# Voltage_Regulation_TI.net
KiCad netlist of a schematic drawn in Altium Designer
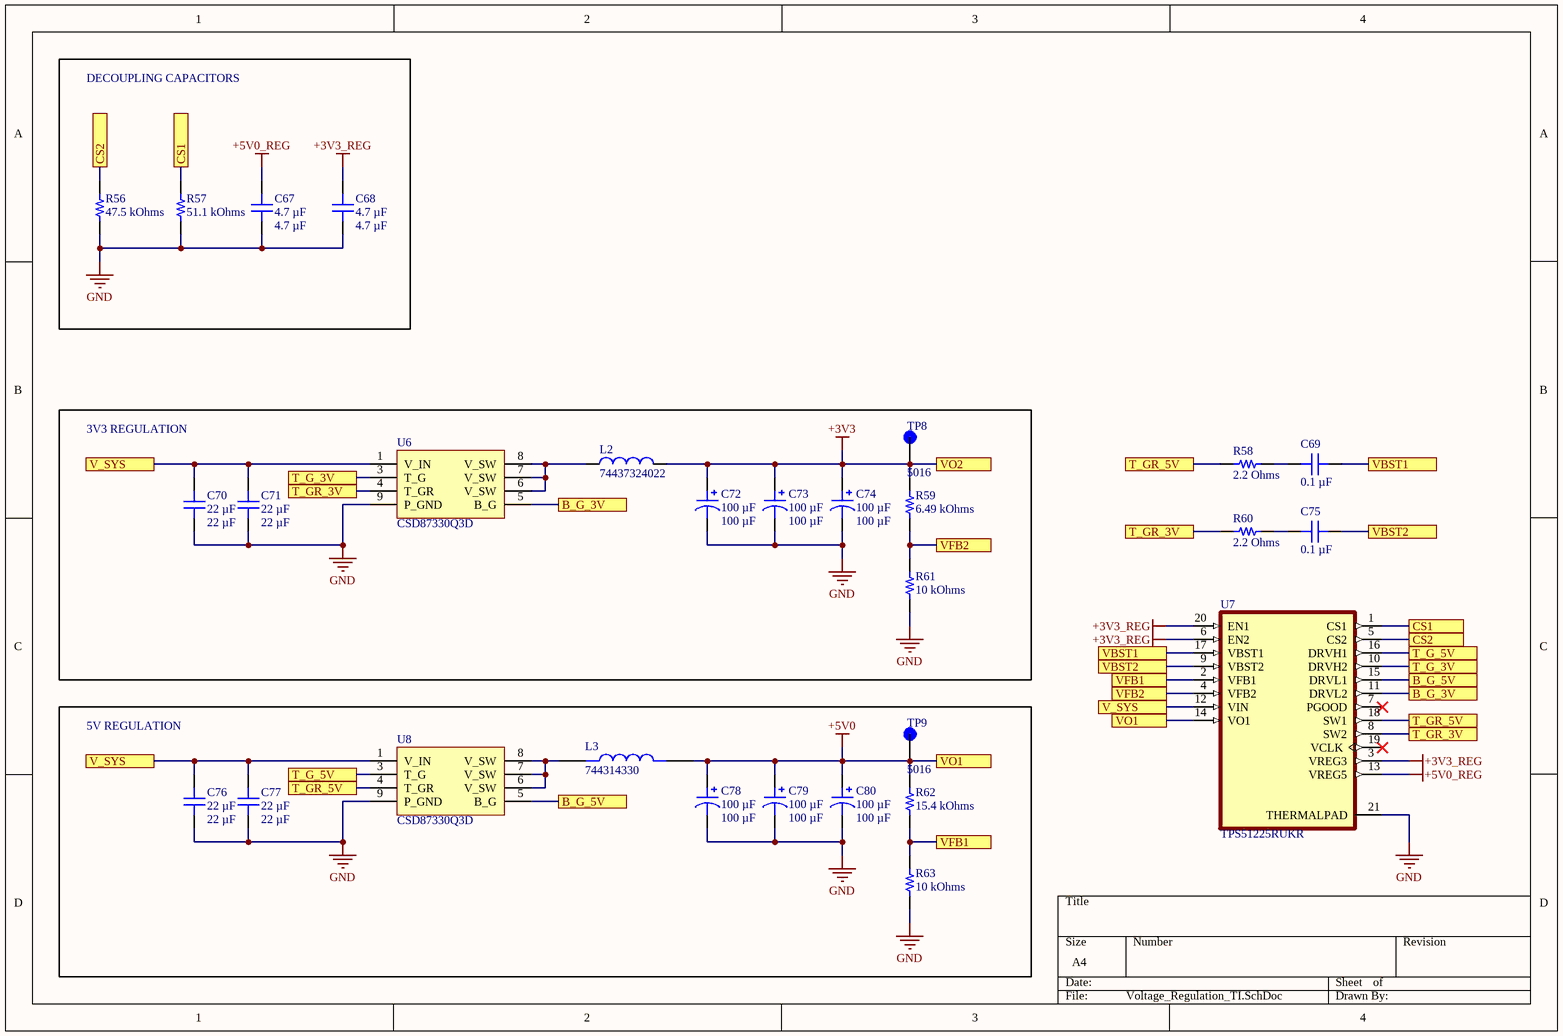
[diagram p0: Voltage_Regulation_TI.SchDoc]

(export (version "E")
  (design (tool "Eeschema 10.0.6"))
  (components
    (comp (ref "C67")
      (value "4.7 µF")
      (footprint "CAP 0402_1005")
      (description "CAP CER 4.7UF 16V X5R 0402")
      (fields
        (field (name "PART NUMBER") "CL05A475MO5NUNC")
        (field (name "ALTIUM_VALUE") "4.7 µF")
        (field (name "MANUFACTURER") "Samsung Electro-Mechanics")
      )
      (libsource (lib "Celestial Altium Library - altium_library") (part "Capacitor"))
    )
    (comp (ref "C68")
      (value "4.7 µF")
      (footprint "CAP 0402_1005")
      (description "CAP CER 4.7UF 16V X5R 0402")
      (fields
        (field (name "PART NUMBER") "CL05A475MO5NUNC")
        (field (name "ALTIUM_VALUE") "4.7 µF")
        (field (name "MANUFACTURER") "Samsung Electro-Mechanics")
      )
      (libsource (lib "Celestial Altium Library - altium_library") (part "Capacitor"))
    )
    (comp (ref "C69")
      (value "0.1 µF")
      (footprint "CAP 0402_1005")
      (description "CAP CER 0.1UF 6.3V X5R 0402")
      (fields (field (name "PART NUMBER") "885012105001") (field (name "MANUFACTURER") "Würth Elektronik"))
      (libsource (lib "Celestial Altium Library - altium_library") (part "Capacitor"))
    )
    (comp (ref "C70")
      (value "22 µF")
      (footprint "CAP 0805_2012")
      (description "CAP CER 22UF 35V X5R 0805")
      (fields
        (field (name "PART NUMBER") "C2012X5R1V226M125AC")
        (field (name "ALTIUM_VALUE") "22 µF")
        (field (name "MANUFACTURER") "TDK Corporation")
      )
      (libsource (lib "Celestial Altium Library - altium_library") (part "Capacitor"))
    )
    (comp (ref "C71")
      (value "22 µF")
      (footprint "CAP 0805_2012")
      (description "CAP CER 22UF 35V X5R 0805")
      (fields
        (field (name "PART NUMBER") "C2012X5R1V226M125AC")
        (field (name "ALTIUM_VALUE") "22 µF")
        (field (name "MANUFACTURER") "TDK Corporation")
      )
      (libsource (lib "Celestial Altium Library - altium_library") (part "Capacitor"))
    )
    (comp (ref "C72")
      (value "100 µF")
      (footprint "CAP POL 1411_3528")
      (description "CAP TANT 100UF 20% 10V 1411")
      (fields
        (field (name "PART NUMBER") "ATCC-211B-010-107M-T")
        (field (name "ALTIUM_VALUE") "100 µF")
        (field (name "MANUFACTURER") "Abracon LLC")
      )
      (libsource (lib "Celestial Altium Library - altium_library") (part "Polarised Capacitor"))
    )
    (comp (ref "C73")
      (value "100 µF")
      (footprint "CAP POL 1411_3528")
      (description "CAP TANT 100UF 20% 10V 1411")
      (fields
        (field (name "PART NUMBER") "ATCC-211B-010-107M-T")
        (field (name "ALTIUM_VALUE") "100 µF")
        (field (name "MANUFACTURER") "Abracon LLC")
      )
      (libsource (lib "Celestial Altium Library - altium_library") (part "Polarised Capacitor"))
    )
    (comp (ref "C74")
      (value "100 µF")
      (footprint "CAP POL 1411_3528")
      (description "CAP TANT 100UF 20% 10V 1411")
      (fields
        (field (name "PART NUMBER") "ATCC-211B-010-107M-T")
        (field (name "ALTIUM_VALUE") "100 µF")
        (field (name "MANUFACTURER") "Abracon LLC")
      )
      (libsource (lib "Celestial Altium Library - altium_library") (part "Polarised Capacitor"))
    )
    (comp (ref "C75")
      (value "0.1 µF")
      (footprint "CAP 0402_1005")
      (description "CAP CER 0.1UF 6.3V X5R 0402")
      (fields (field (name "PART NUMBER") "885012105001") (field (name "MANUFACTURER") "Würth Elektronik"))
      (libsource (lib "Celestial Altium Library - altium_library") (part "Capacitor"))
    )
    (comp (ref "C76")
      (value "22 µF")
      (footprint "CAP 0805_2012")
      (description "CAP CER 22UF 35V X5R 0805")
      (fields
        (field (name "PART NUMBER") "C2012X5R1V226M125AC")
        (field (name "ALTIUM_VALUE") "22 µF")
        (field (name "MANUFACTURER") "TDK Corporation")
      )
      (libsource (lib "Celestial Altium Library - altium_library") (part "Capacitor"))
    )
    (comp (ref "C77")
      (value "22 µF")
      (footprint "CAP 0805_2012")
      (description "CAP CER 22UF 35V X5R 0805")
      (fields
        (field (name "PART NUMBER") "C2012X5R1V226M125AC")
        (field (name "ALTIUM_VALUE") "22 µF")
        (field (name "MANUFACTURER") "TDK Corporation")
      )
      (libsource (lib "Celestial Altium Library - altium_library") (part "Capacitor"))
    )
    (comp (ref "C78")
      (value "100 µF")
      (footprint "CAP POL 1411_3528")
      (description "CAP TANT 100UF 20% 10V 1411")
      (fields
        (field (name "PART NUMBER") "ATCC-211B-010-107M-T")
        (field (name "ALTIUM_VALUE") "100 µF")
        (field (name "MANUFACTURER") "Abracon LLC")
      )
      (libsource (lib "Celestial Altium Library - altium_library") (part "Polarised Capacitor"))
    )
    (comp (ref "C79")
      (value "100 µF")
      (footprint "CAP POL 1411_3528")
      (description "CAP TANT 100UF 20% 10V 1411")
      (fields
        (field (name "PART NUMBER") "ATCC-211B-010-107M-T")
        (field (name "ALTIUM_VALUE") "100 µF")
        (field (name "MANUFACTURER") "Abracon LLC")
      )
      (libsource (lib "Celestial Altium Library - altium_library") (part "Polarised Capacitor"))
    )
    (comp (ref "C80")
      (value "100 µF")
      (footprint "CAP POL 1411_3528")
      (description "CAP TANT 100UF 20% 10V 1411")
      (fields
        (field (name "PART NUMBER") "ATCC-211B-010-107M-T")
        (field (name "ALTIUM_VALUE") "100 µF")
        (field (name "MANUFACTURER") "Abracon LLC")
      )
      (libsource (lib "Celestial Altium Library - altium_library") (part "Polarised Capacitor"))
    )
    (comp (ref "L2")
      (value "74437324022")
      (footprint "74437324022:IND_74437324022")
      (description "LHMI Inductor 4020 2.2uH 5.0A 27.0mOhm")
      (fields (field (name "MF") "{'manufacturer': u'~{W}xfcrth Elektronik'}"))
      (libsource (lib "*") (part "74437324022"))
    )
    (comp (ref "L3")
      (value "744314330")
      (footprint "744314330:IND_744314330")
      (description "Inductor SMD 7050 3.3µH 9 A Wuerth Elektronik WE-HCI 744314330 1 pc(s)")
      (fields (field (name "MF") "{'manufacturer': u'Wurth Electronics'}"))
      (libsource (lib "*") (part "744314330"))
    )
    (comp (ref "R56")
      (value "47.5 kOhms")
      (footprint "RES 0402_1005")
      (description "RES 47.5K OHM 1% 1/16W 0402")
      (fields (field (name "PART NUMBER") "RC0402FR-0747K5L") (field (name "MANUFACTURER") "Yageo"))
      (libsource (lib "Celestial Altium Library - altium_library") (part "Resistor"))
    )
    (comp (ref "R57")
      (value "51.1 kOhms")
      (footprint "RES 0402_1005")
      (description "RES SMD 51.1K OHM 1% 1/16W 0402")
      (fields (field (name "PART NUMBER") "CR0402-FX-5112GLF") (field (name "MANUFACTURER") "Bourns Inc."))
      (libsource (lib "Celestial Altium Library - altium_library") (part "Resistor"))
    )
    (comp (ref "R58")
      (value "2.2 Ohms")
      (footprint "RES 0402_1005")
      (description "RES 2.2 OHM 5% 1/16W 0402")
      (fields (field (name "PART NUMBER") "RC0402JR-072R2L") (field (name "MANUFACTURER") "Yageo"))
      (libsource (lib "Celestial Altium Library - altium_library") (part "Resistor"))
    )
    (comp (ref "R59")
      (value "6.49 kOhms")
      (footprint "RES 0402_1005")
      (description "RES 6.49K OHM 1% 1/16W 0402")
      (fields (field (name "PART NUMBER") "RC0402FR-076K49L") (field (name "MANUFACTURER") "Yageo"))
      (libsource (lib "Celestial Altium Library - altium_library") (part "Resistor"))
    )
    (comp (ref "R60")
      (value "2.2 Ohms")
      (footprint "RES 0402_1005")
      (description "RES 2.2 OHM 5% 1/16W 0402")
      (fields (field (name "PART NUMBER") "RC0402JR-072R2L") (field (name "MANUFACTURER") "Yageo"))
      (libsource (lib "Celestial Altium Library - altium_library") (part "Resistor"))
    )
    (comp (ref "R61")
      (value "10 kOhms")
      (footprint "RES 0402_1005")
      (description "RES 10K OHM 5% 1/16W 0402")
      (fields (field (name "PART NUMBER") "RC0402JR-1310KL") (field (name "MANUFACTURER") "Yageo"))
      (libsource (lib "Celestial Altium Library - altium_library") (part "Resistor"))
    )
    (comp (ref "R62")
      (value "15.4 kOhms")
      (footprint "RES 0402_1005")
      (description "RES 15.4K OHM 1% 1/16W 0402")
      (fields (field (name "PART NUMBER") "RC0402FR-0715K4L") (field (name "MANUFACTURER") "Yageo"))
      (libsource (lib "Celestial Altium Library - altium_library") (part "Resistor"))
    )
    (comp (ref "R63")
      (value "10 kOhms")
      (footprint "RES 0402_1005")
      (description "RES 10K OHM 5% 1/16W 0402")
      (fields (field (name "PART NUMBER") "RC0402JR-1310KL") (field (name "MANUFACTURER") "Yageo"))
      (libsource (lib "Celestial Altium Library - altium_library") (part "Resistor"))
    )
    (comp (ref "TP8")
      (value "5016")
      (footprint "5016:KEYSTONE_5016")
      (fields (field (name "MF") "{'manufacturer': u'Keystone Electronics'}"))
      (libsource (lib "*") (part "5016"))
    )
    (comp (ref "TP9")
      (value "5016")
      (footprint "5016:KEYSTONE_5016")
      (fields (field (name "MF") "{'manufacturer': u'Keystone Electronics'}"))
      (libsource (lib "*") (part "5016"))
    )
    (comp (ref "U6")
      (value "CSD87330Q3D")
      (footprint "Q3D")
      (description "Synchronous Buck NexFET™ Power Block")
      (libsource (lib "Schlib2") (part "CSD87330Q3D"))
    )
    (comp (ref "U7")
      (value "TPS51225RUKR")
      (footprint "TPS51225RUKR:QFN40P300X300X80-21N")
      (fields (field (name "MF") "{'manufacturer': u'Texas Instruments'}"))
      (libsource (lib "*") (part "TPS51225RUKR"))
    )
    (comp (ref "U8")
      (value "CSD87330Q3D")
      (footprint "Q3D")
      (description "Synchronous Buck NexFET™ Power Block")
      (libsource (lib "Schlib2") (part "CSD87330Q3D"))
    )
  )
  (nets
    (net (code "1") (name "+3V3") (class "Default")
      (node (ref "C72") (pin "1") (pinfunction "1_1") (pintype "passive"))
      (node (ref "C73") (pin "1") (pinfunction "1_1") (pintype "passive"))
      (node (ref "C74") (pin "1") (pinfunction "1_1") (pintype "passive"))
      (node (ref "L2") (pin "2") (pinfunction "2_2") (pintype "passive"))
      (node (ref "R59") (pin "2") (pinfunction "2_2") (pintype "passive"))
      (node (ref "TP8") (pin "TP") (pinfunction "TP_TP") (pintype "passive"))
    )
    (net (code "2") (name "+3V3_REG") (class "Default")
      (node (ref "C68") (pin "2") (pinfunction "2_2") (pintype "passive"))
      (node (ref "U7") (pin "20") (pinfunction "EN1_20") (pintype "input"))
      (node (ref "U7") (pin "3") (pinfunction "VREG3_3") (pintype "output"))
      (node (ref "U7") (pin "6") (pinfunction "EN2_6") (pintype "input"))
    )
    (net (code "3") (name "+5V0") (class "Default")
      (node (ref "C78") (pin "1") (pinfunction "1_1") (pintype "passive"))
      (node (ref "C79") (pin "1") (pinfunction "1_1") (pintype "passive"))
      (node (ref "C80") (pin "1") (pinfunction "1_1") (pintype "passive"))
      (node (ref "L3") (pin "2") (pinfunction "2_2") (pintype "passive"))
      (node (ref "R62") (pin "2") (pinfunction "2_2") (pintype "passive"))
      (node (ref "TP9") (pin "TP") (pinfunction "TP_TP") (pintype "passive"))
      (node (ref "U7") (pin "14") (pinfunction "VO1_14") (pintype "input"))
    )
    (net (code "4") (name "+5V0_REG") (class "Default")
      (node (ref "C67") (pin "2") (pinfunction "2_2") (pintype "passive"))
      (node (ref "U7") (pin "13") (pinfunction "VREG5_13") (pintype "output"))
    )
    (net (code "5") (name "/B_G_3V") (class "Default")
      (node (ref "U6") (pin "5") (pinfunction "B_G_5") (pintype "passive"))
      (node (ref "U7") (pin "11") (pinfunction "DRVL2_11") (pintype "output"))
    )
    (net (code "6") (name "/B_G_5V") (class "Default")
      (node (ref "U7") (pin "15") (pinfunction "DRVL1_15") (pintype "output"))
      (node (ref "U8") (pin "5") (pinfunction "B_G_5") (pintype "passive"))
    )
    (net (code "7") (name "/CS1") (class "Default")
      (node (ref "R57") (pin "2") (pinfunction "2_2") (pintype "passive"))
      (node (ref "U7") (pin "1") (pinfunction "CS1_1") (pintype "output"))
    )
    (net (code "8") (name "/CS2") (class "Default")
      (node (ref "R56") (pin "2") (pinfunction "2_2") (pintype "passive"))
      (node (ref "U7") (pin "5") (pinfunction "CS2_5") (pintype "output"))
    )
    (net (code "9") (name "/T_GR_3V") (class "Default")
      (node (ref "R60") (pin "1") (pinfunction "1_1") (pintype "passive"))
      (node (ref "U6") (pin "4") (pinfunction "T_GR_4") (pintype "passive"))
      (node (ref "U7") (pin "8") (pinfunction "SW2_8") (pintype "output"))
    )
    (net (code "10") (name "/T_GR_5V") (class "Default")
      (node (ref "R58") (pin "1") (pinfunction "1_1") (pintype "passive"))
      (node (ref "U7") (pin "18") (pinfunction "SW1_18") (pintype "output"))
      (node (ref "U8") (pin "4") (pinfunction "T_GR_4") (pintype "passive"))
    )
    (net (code "11") (name "/T_G_3V") (class "Default")
      (node (ref "U6") (pin "3") (pinfunction "T_G_3") (pintype "passive"))
      (node (ref "U7") (pin "10") (pinfunction "DRVH2_10") (pintype "output"))
    )
    (net (code "12") (name "/T_G_5V") (class "Default")
      (node (ref "U7") (pin "16") (pinfunction "DRVH1_16") (pintype "output"))
      (node (ref "U8") (pin "3") (pinfunction "T_G_3") (pintype "passive"))
    )
    (net (code "13") (name "/VBST1") (class "Default")
      (node (ref "C69") (pin "1") (pinfunction "1_1") (pintype "passive"))
      (node (ref "U7") (pin "17") (pinfunction "VBST1_17") (pintype "input"))
    )
    (net (code "14") (name "/VBST2") (class "Default")
      (node (ref "C75") (pin "1") (pinfunction "1_1") (pintype "passive"))
      (node (ref "U7") (pin "9") (pinfunction "VBST2_9") (pintype "input"))
    )
    (net (code "15") (name "/VFB1") (class "Default")
      (node (ref "R62") (pin "1") (pinfunction "1_1") (pintype "passive"))
      (node (ref "R63") (pin "1") (pinfunction "1_1") (pintype "passive"))
      (node (ref "U7") (pin "2") (pinfunction "VFB1_2") (pintype "input"))
    )
    (net (code "16") (name "/VFB2") (class "Default")
      (node (ref "R59") (pin "1") (pinfunction "1_1") (pintype "passive"))
      (node (ref "R61") (pin "1") (pinfunction "1_1") (pintype "passive"))
      (node (ref "U7") (pin "4") (pinfunction "VFB2_4") (pintype "input"))
    )
    (net (code "17") (name "/V_SYS") (class "Default")
      (node (ref "C70") (pin "2") (pinfunction "2_2") (pintype "passive"))
      (node (ref "C71") (pin "2") (pinfunction "2_2") (pintype "passive"))
      (node (ref "C76") (pin "2") (pinfunction "2_2") (pintype "passive"))
      (node (ref "C77") (pin "2") (pinfunction "2_2") (pintype "passive"))
      (node (ref "U6") (pin "1") (pinfunction "V_IN_1") (pintype "passive"))
      (node (ref "U7") (pin "12") (pinfunction "VIN_12") (pintype "input"))
      (node (ref "U8") (pin "1") (pinfunction "V_IN_1") (pintype "passive"))
    )
    (net (code "18") (name "GND") (class "Default")
      (node (ref "C67") (pin "1") (pinfunction "1_1") (pintype "passive"))
      (node (ref "C68") (pin "1") (pinfunction "1_1") (pintype "passive"))
      (node (ref "C70") (pin "1") (pinfunction "1_1") (pintype "passive"))
      (node (ref "C71") (pin "1") (pinfunction "1_1") (pintype "passive"))
      (node (ref "C72") (pin "2") (pinfunction "2_2") (pintype "passive"))
      (node (ref "C73") (pin "2") (pinfunction "2_2") (pintype "passive"))
      (node (ref "C74") (pin "2") (pinfunction "2_2") (pintype "passive"))
      (node (ref "C76") (pin "1") (pinfunction "1_1") (pintype "passive"))
      (node (ref "C77") (pin "1") (pinfunction "1_1") (pintype "passive"))
      (node (ref "C78") (pin "2") (pinfunction "2_2") (pintype "passive"))
      (node (ref "C79") (pin "2") (pinfunction "2_2") (pintype "passive"))
      (node (ref "C80") (pin "2") (pinfunction "2_2") (pintype "passive"))
      (node (ref "R56") (pin "1") (pinfunction "1_1") (pintype "passive"))
      (node (ref "R57") (pin "1") (pinfunction "1_1") (pintype "passive"))
      (node (ref "R61") (pin "2") (pinfunction "2_2") (pintype "passive"))
      (node (ref "R63") (pin "2") (pinfunction "2_2") (pintype "passive"))
      (node (ref "U6") (pin "9") (pinfunction "P_GND_9") (pintype "passive"))
      (node (ref "U7") (pin "21") (pinfunction "THERMALPAD_21") (pintype "power_in"))
      (node (ref "U8") (pin "9") (pinfunction "P_GND_9") (pintype "passive"))
    )
    (net (code "19") (name "Net-(C69-Pad2)") (class "Default")
      (node (ref "C69") (pin "2") (pinfunction "2_2") (pintype "passive"))
      (node (ref "R58") (pin "2") (pinfunction "2_2") (pintype "passive"))
    )
    (net (code "20") (name "Net-(C75-Pad2)") (class "Default")
      (node (ref "C75") (pin "2") (pinfunction "2_2") (pintype "passive"))
      (node (ref "R60") (pin "2") (pinfunction "2_2") (pintype "passive"))
    )
    (net (code "21") (name "Net-(L2-Pad1)") (class "Default")
      (node (ref "L2") (pin "1") (pinfunction "1_1") (pintype "passive"))
      (node (ref "U6") (pin "6") (pinfunction "V_SW_6") (pintype "passive"))
      (node (ref "U6") (pin "7") (pinfunction "V_SW_7") (pintype "passive"))
      (node (ref "U6") (pin "8") (pinfunction "V_SW_8") (pintype "passive"))
    )
    (net (code "22") (name "Net-(L3-Pad1)") (class "Default")
      (node (ref "L3") (pin "1") (pinfunction "1_1") (pintype "passive"))
      (node (ref "U8") (pin "6") (pinfunction "V_SW_6") (pintype "passive"))
      (node (ref "U8") (pin "7") (pinfunction "V_SW_7") (pintype "passive"))
      (node (ref "U8") (pin "8") (pinfunction "V_SW_8") (pintype "passive"))
    )
    (net (code "23") (name "unconnected-(U7-PGOOD-Pad7)") (class "Default")
      (node (ref "U7") (pin "7") (pinfunction "PGOOD_7") (pintype "output+no_connect"))
    )
    (net (code "24") (name "unconnected-(U7-VCLK-Pad19)") (class "Default")
      (node (ref "U7") (pin "19") (pinfunction "VCLK_19") (pintype "output+no_connect"))
    )
  )
)
